# sensor.net
KiCad netlist of a schematic drawn in Altium Designer
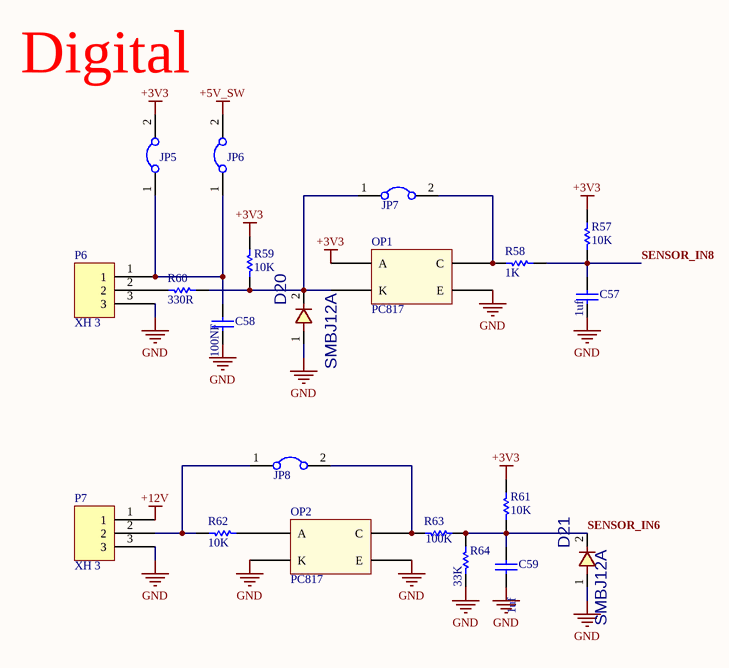
[diagram p0: sensor.SchDoc]

(export (version "E")
  (design (tool "Eeschema 10.0.6"))
  (components
    (comp (ref "C57")
      (value "1uf")
      (footprint "CAP0603")
      (description "TOTAL CAPACITOR SMD PACK")
      (fields (field (name "DESIGNER") "Abbas Basereh"))
      (libsource (lib "Altium") (part "CAP SMD PACKAGE"))
    )
    (comp (ref "C58")
      (value "100NF")
      (footprint "CAP0603")
      (description "TOTAL CAPACITOR SMD PACK")
      (fields (field (name "DESIGNER") "Abbas Basereh"))
      (libsource (lib "Altium") (part "CAP SMD PACKAGE"))
    )
    (comp (ref "C59")
      (value "1uf")
      (footprint "CAP0603")
      (description "TOTAL CAPACITOR SMD PACK")
      (fields (field (name "DESIGNER") "Abbas Basereh"))
      (libsource (lib "Altium") (part "CAP SMD PACKAGE"))
    )
    (comp (ref "D20")
      (value "SMBJ12A")
      (footprint "D_SMB")
      (description "TVS Surface Mount Transient Voltage Suppressors Diode")
      (fields (field (name "Comment") "SMBJ12A-TR SMD"))
      (libsource (lib "altium-import") (part "root_1_SMBJ12A-TR SMD_"))
    )
    (comp (ref "D21")
      (value "SMBJ12A")
      (footprint "D_SMB")
      (description "TVS Surface Mount Transient Voltage Suppressors Diode")
      (fields (field (name "Comment") "SMBJ12A-TR SMD"))
      (libsource (lib "altium-import") (part "root_1_SMBJ12A-TR SMD_"))
    )
    (comp (ref "JP5")
      (value "Jumper")
      (footprint "Jumper Small - 2.54 - GRAY")
      (libsource (lib "altium-import") (part "root_1_Jumper_"))
    )
    (comp (ref "JP6")
      (value "Jumper")
      (footprint "Jumper Small - 2.54 - GRAY")
      (libsource (lib "altium-import") (part "root_1_Jumper_"))
    )
    (comp (ref "JP7")
      (value "Jumper")
      (footprint "Jumper Small - 2.54 - GRAY")
      (libsource (lib "altium-import") (part "root_0_Jumper_"))
    )
    (comp (ref "JP8")
      (value "Jumper")
      (footprint "Jumper Small - 2.54 - GRAY")
      (libsource (lib "altium-import") (part "root_0_Jumper_"))
    )
    (comp (ref "OP1")
      (value "PC817")
      (footprint "PC817 SMD")
      (description "PC817 optocpler")
      (libsource (lib "IC") (part "PC817"))
    )
    (comp (ref "OP2")
      (value "PC817")
      (footprint "PC817 SMD")
      (description "PC817 optocpler")
      (libsource (lib "IC") (part "PC817"))
    )
    (comp (ref "P6")
      (value "XH 3")
      (footprint "XH 3 PIN")
      (description "Conector XH 3 Pin")
      (libsource (lib "altium-import") (part "root_1_Conector XH 3 Pin_"))
    )
    (comp (ref "P7")
      (value "XH 3")
      (footprint "XH 3 PIN")
      (description "Conector XH 3 Pin")
      (libsource (lib "altium-import") (part "root_1_Conector XH 3 Pin_"))
    )
    (comp (ref "R57")
      (value "10K")
      (footprint "R0603")
      (description "Resistor SMD 0603")
      (libsource (lib "Resistor") (part "Resistor SMD 0603"))
    )
    (comp (ref "R58")
      (value "1K")
      (footprint "R0603")
      (description "Resistor SMD 0603")
      (libsource (lib "Resistor") (part "Resistor SMD 0603"))
    )
    (comp (ref "R59")
      (value "10K")
      (footprint "R0603")
      (description "Resistor SMD 0603")
      (libsource (lib "Resistor") (part "Resistor SMD 0603"))
    )
    (comp (ref "R60")
      (value "330R")
      (footprint "R0603")
      (description "Resistor SMD 0603")
      (libsource (lib "Resistor") (part "Resistor SMD 0603"))
    )
    (comp (ref "R61")
      (value "10K")
      (footprint "R0603")
      (description "Resistor SMD 0603")
      (libsource (lib "Resistor") (part "Resistor SMD 0603"))
    )
    (comp (ref "R62")
      (value "10K")
      (footprint "R0603")
      (description "Resistor SMD 0603")
      (libsource (lib "Resistor") (part "Resistor SMD 0603"))
    )
    (comp (ref "R63")
      (value "100K")
      (footprint "R0603")
      (description "Resistor SMD 0603")
      (libsource (lib "Resistor") (part "Resistor SMD 0603"))
    )
    (comp (ref "R64")
      (value "33K")
      (footprint "R0603")
      (description "Resistor SMD 0603")
      (libsource (lib "Resistor") (part "Resistor SMD 0603"))
    )
  )
  (nets
    (net (code "1") (name "+3V3") (class "Default")
      (node (ref "JP5") (pin "2") (pinfunction "2_2") (pintype "passive"))
      (node (ref "OP1") (pin "1") (pinfunction "A_1") (pintype "passive"))
      (node (ref "R57") (pin "2") (pinfunction "2_2") (pintype "passive"))
      (node (ref "R59") (pin "2") (pinfunction "2_2") (pintype "passive"))
      (node (ref "R61") (pin "2") (pinfunction "2_2") (pintype "passive"))
    )
    (net (code "2") (name "+5V_SW") (class "Default")
      (node (ref "JP6") (pin "2") (pinfunction "2_2") (pintype "passive"))
    )
    (net (code "3") (name "+12V") (class "Default")
      (node (ref "P7") (pin "1") (pinfunction "1_1") (pintype "passive"))
    )
    (net (code "4") (name "/SENSOR_IN6") (class "Default")
      (node (ref "C59") (pin "2") (pinfunction "2_2") (pintype "passive"))
      (node (ref "D21") (pin "2") (pinfunction "2_2") (pintype "passive"))
      (node (ref "R61") (pin "1") (pinfunction "1_1") (pintype "passive"))
      (node (ref "R63") (pin "2") (pinfunction "2_2") (pintype "passive"))
      (node (ref "R64") (pin "2") (pinfunction "2_2") (pintype "passive"))
    )
    (net (code "5") (name "/SENSOR_IN8") (class "Default")
      (node (ref "C57") (pin "2") (pinfunction "2_2") (pintype "passive"))
      (node (ref "R57") (pin "1") (pinfunction "1_1") (pintype "passive"))
      (node (ref "R58") (pin "2") (pinfunction "2_2") (pintype "passive"))
    )
    (net (code "6") (name "GND") (class "Default")
      (node (ref "C57") (pin "1") (pinfunction "1_1") (pintype "passive"))
      (node (ref "C58") (pin "1") (pinfunction "1_1") (pintype "passive"))
      (node (ref "C59") (pin "1") (pinfunction "1_1") (pintype "passive"))
      (node (ref "D20") (pin "1") (pinfunction "1_1") (pintype "passive"))
      (node (ref "D21") (pin "1") (pinfunction "1_1") (pintype "passive"))
      (node (ref "OP1") (pin "3") (pinfunction "E_3") (pintype "passive"))
      (node (ref "OP2") (pin "2") (pinfunction "K_2") (pintype "passive"))
      (node (ref "OP2") (pin "3") (pinfunction "E_3") (pintype "passive"))
      (node (ref "P6") (pin "3") (pinfunction "3_3") (pintype "passive"))
      (node (ref "P7") (pin "3") (pinfunction "3_3") (pintype "passive"))
      (node (ref "R64") (pin "1") (pinfunction "1_1") (pintype "passive"))
    )
    (net (code "7") (name "Net-(C58-Pad2)") (class "Default")
      (node (ref "C58") (pin "2") (pinfunction "2_2") (pintype "passive"))
      (node (ref "JP5") (pin "1") (pinfunction "1_1") (pintype "passive"))
      (node (ref "JP6") (pin "1") (pinfunction "1_1") (pintype "passive"))
      (node (ref "P6") (pin "1") (pinfunction "1_1") (pintype "passive"))
    )
    (net (code "8") (name "Net-(JP8-Pad1)") (class "Default")
      (node (ref "JP8") (pin "1") (pinfunction "1_1") (pintype "passive"))
      (node (ref "P7") (pin "2") (pinfunction "2_2") (pintype "passive"))
      (node (ref "R62") (pin "1") (pinfunction "1_1") (pintype "passive"))
    )
    (net (code "9") (name "Net-(OP1-C)") (class "Default")
      (node (ref "JP7") (pin "2") (pinfunction "2_2") (pintype "passive"))
      (node (ref "OP1") (pin "4") (pinfunction "C_4") (pintype "passive"))
      (node (ref "R58") (pin "1") (pinfunction "1_1") (pintype "passive"))
    )
    (net (code "10") (name "Net-(OP1-K)") (class "Default")
      (node (ref "D20") (pin "2") (pinfunction "2_2") (pintype "passive"))
      (node (ref "JP7") (pin "1") (pinfunction "1_1") (pintype "passive"))
      (node (ref "OP1") (pin "2") (pinfunction "K_2") (pintype "passive"))
      (node (ref "R59") (pin "1") (pinfunction "1_1") (pintype "passive"))
      (node (ref "R60") (pin "2") (pinfunction "2_2") (pintype "passive"))
    )
    (net (code "11") (name "Net-(OP2-A)") (class "Default")
      (node (ref "OP2") (pin "1") (pinfunction "A_1") (pintype "passive"))
      (node (ref "R62") (pin "2") (pinfunction "2_2") (pintype "passive"))
    )
    (net (code "12") (name "Net-(OP2-C)") (class "Default")
      (node (ref "JP8") (pin "2") (pinfunction "2_2") (pintype "passive"))
      (node (ref "OP2") (pin "4") (pinfunction "C_4") (pintype "passive"))
      (node (ref "R63") (pin "1") (pinfunction "1_1") (pintype "passive"))
    )
    (net (code "13") (name "Net-(P6-Pad2)") (class "Default")
      (node (ref "P6") (pin "2") (pinfunction "2_2") (pintype "passive"))
      (node (ref "R60") (pin "1") (pinfunction "1_1") (pintype "passive"))
    )
  )
)
